# Arduino-Pro-Mini-v10.net
KiCad netlist of a schematic drawn in EAGLE
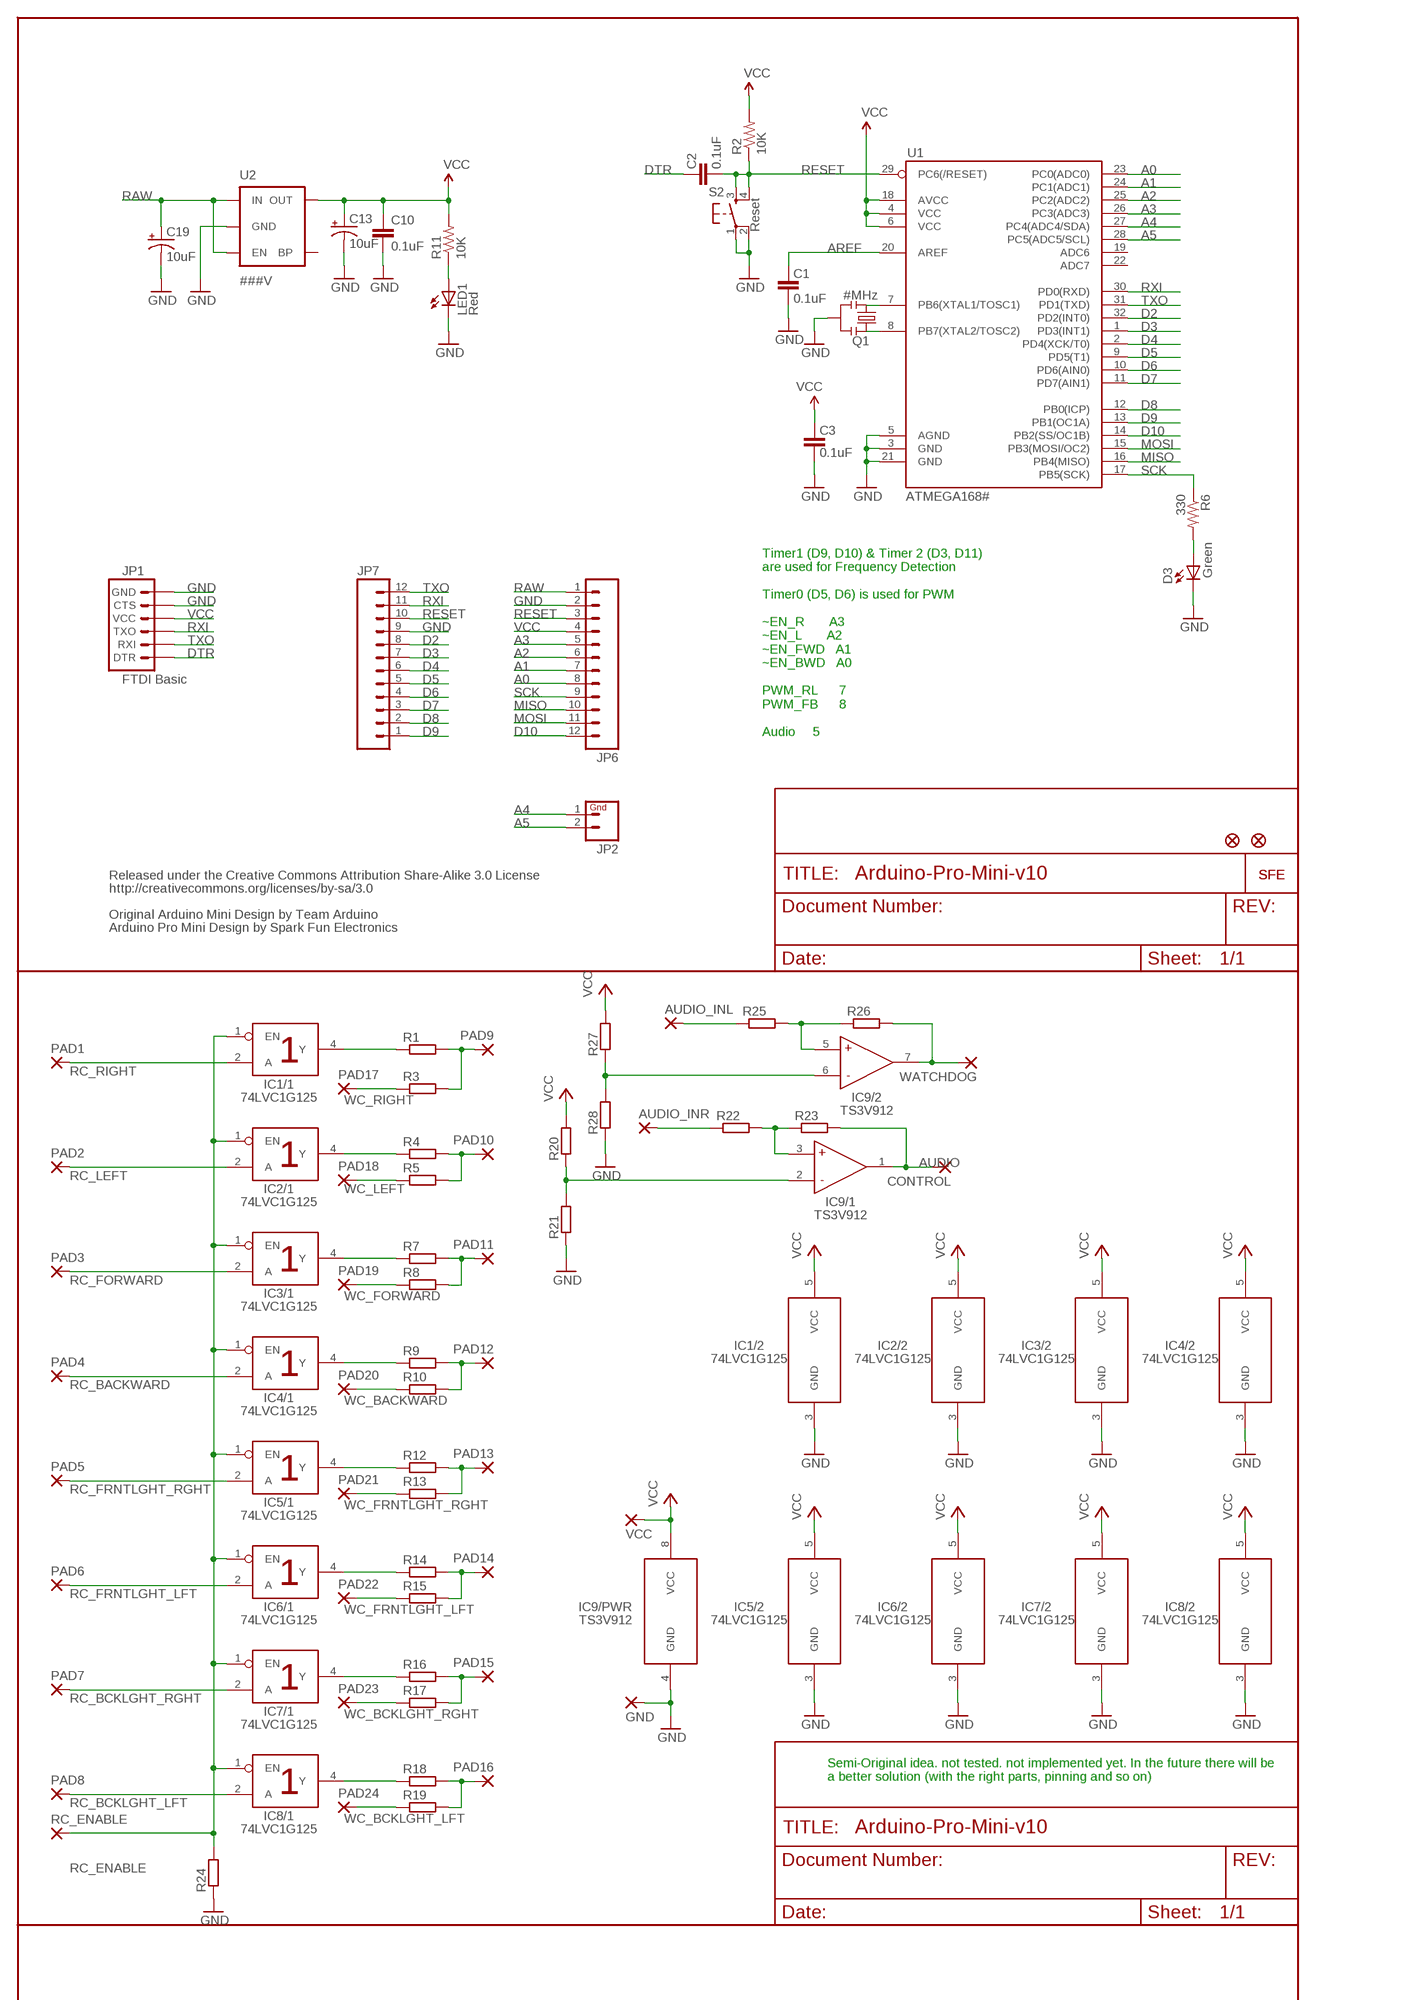
[diagram p0: schematic, sheet 1, part 1 of 2]
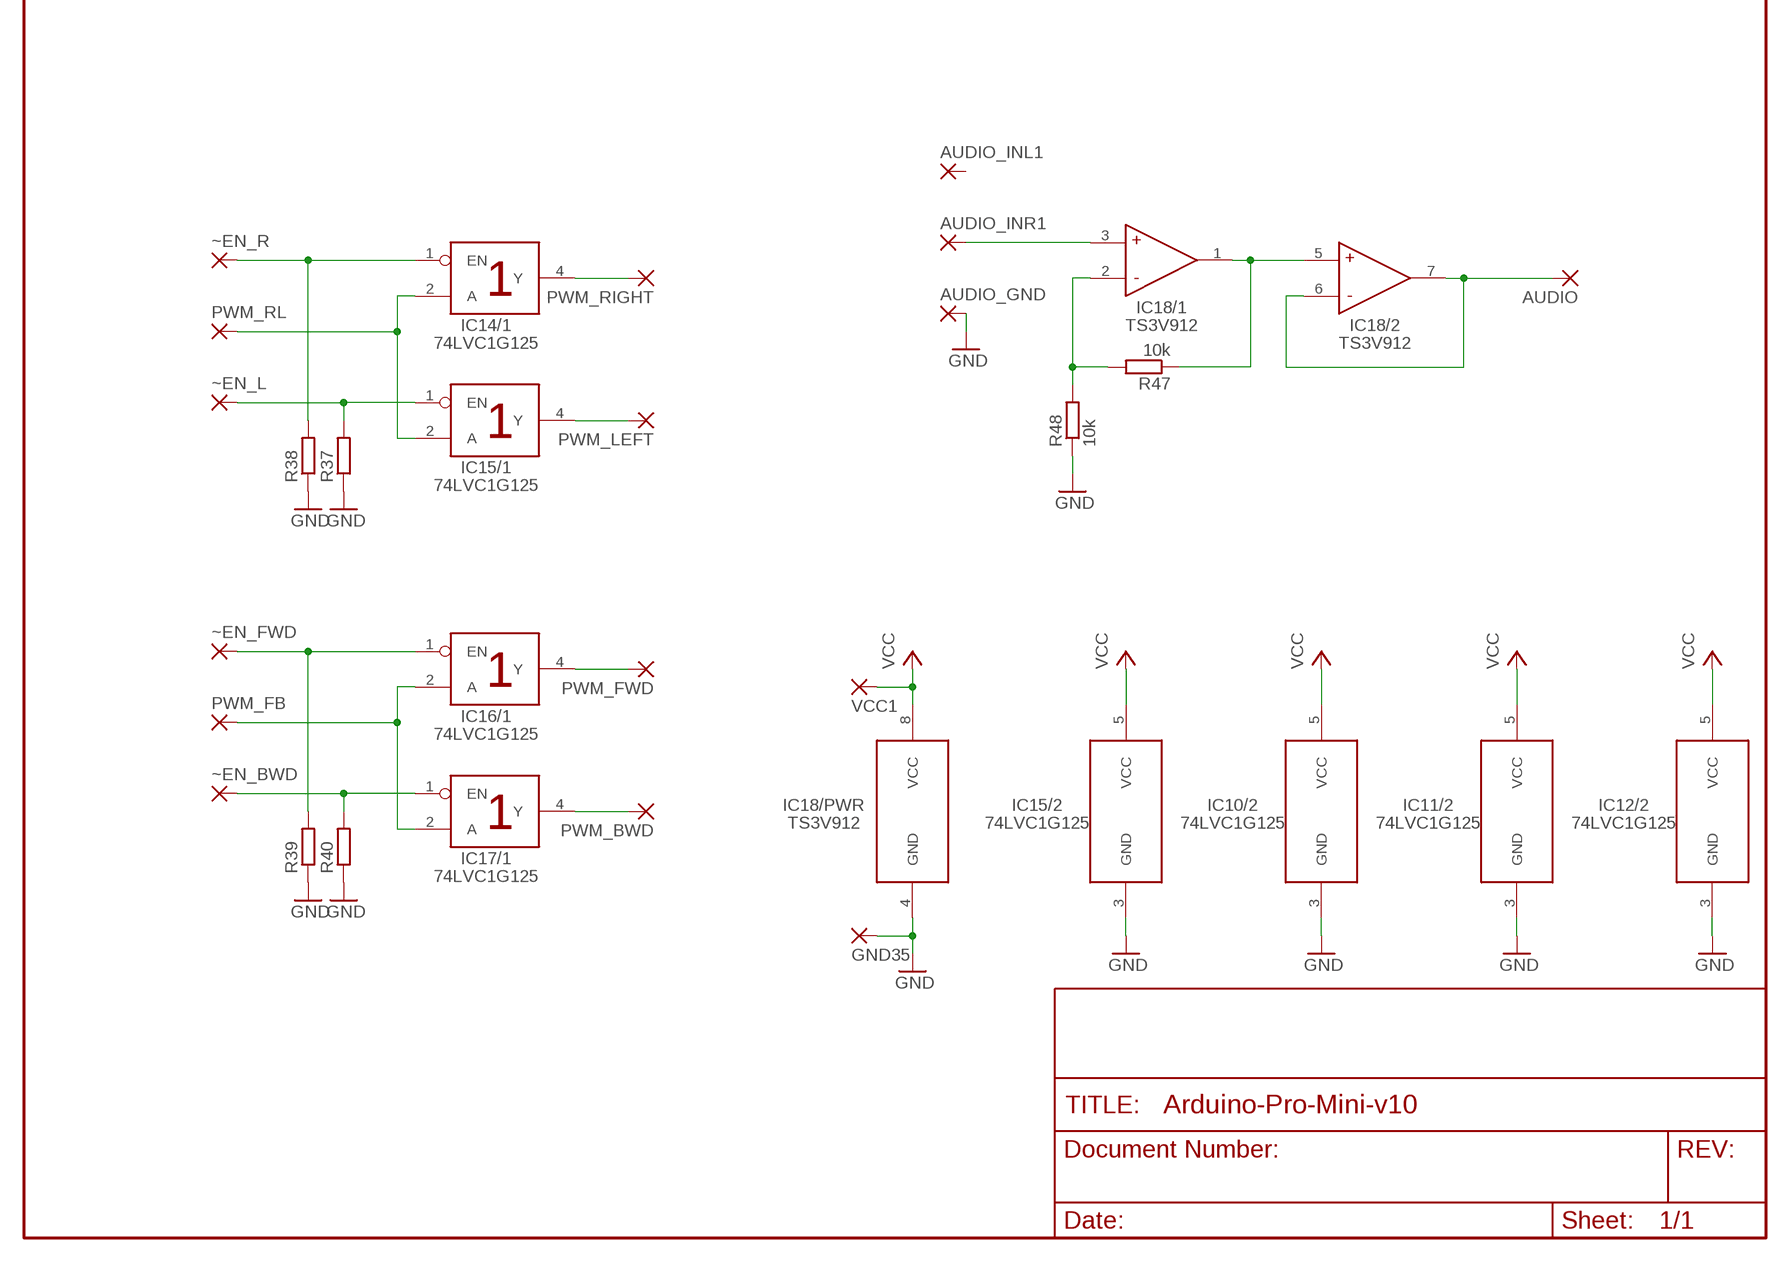
[diagram p1: schematic, sheet 1, part 2 of 2]

(export (version "E")
  (design (tool "Eeschema 10.0.6"))
  (components
    (comp (ref "AUDIO")
      (value "SMD2")
      (footprint "eagle-import:SMD1,27-2,54")
      (libsource (lib "eagle-import") (part "SMD2"))
    )
    (comp (ref "AUDIO_GND")
      (value "SMD2")
      (footprint "eagle-import:SMD1,27-2,54")
      (libsource (lib "eagle-import") (part "SMD2"))
    )
    (comp (ref "AUDIO_INL")
      (value "SMD2")
      (footprint "eagle-import:SMD1,27-2,54")
      (libsource (lib "eagle-import") (part "SMD2"))
    )
    (comp (ref "AUDIO_INL1")
      (value "SMD2")
      (footprint "eagle-import:SMD1,27-2,54")
      (libsource (lib "eagle-import") (part "SMD2"))
    )
    (comp (ref "AUDIO_INR")
      (value "SMD2")
      (footprint "eagle-import:SMD1,27-2,54")
      (libsource (lib "eagle-import") (part "SMD2"))
    )
    (comp (ref "AUDIO_INR1")
      (value "SMD2")
      (footprint "eagle-import:SMD1,27-2,54")
      (libsource (lib "eagle-import") (part "SMD2"))
    )
    (comp (ref "C1")
      (value "0.1uF")
      (footprint "eagle-import:C0402")
      (libsource (lib "eagle-import") (part "CAP0402"))
    )
    (comp (ref "C2")
      (value "0.1uF")
      (footprint "eagle-import:C0402")
      (libsource (lib "eagle-import") (part "CAP0402"))
    )
    (comp (ref "C3")
      (value "0.1uF")
      (footprint "eagle-import:C0402")
      (libsource (lib "eagle-import") (part "CAP0402"))
    )
    (comp (ref "C10")
      (value "0.1uF")
      (footprint "eagle-import:C0402")
      (libsource (lib "eagle-import") (part "CAP0402"))
    )
    (comp (ref "C13")
      (value "10uF")
      (footprint "eagle-import:EIA3216")
      (libsource (lib "eagle-import") (part "CAP_POL1206"))
    )
    (comp (ref "C19")
      (value "10uF")
      (footprint "eagle-import:EIA3216")
      (libsource (lib "eagle-import") (part "CAP_POL1206"))
    )
    (comp (ref "CONTROL")
      (value "SMD2")
      (footprint "eagle-import:SMD1,27-2,54")
      (libsource (lib "eagle-import") (part "SMD2"))
    )
    (comp (ref "D3")
      (value "Green")
      (footprint "eagle-import:LED-0603")
      (libsource (lib "eagle-import") (part "LED0603"))
    )
    (comp (ref "GND")
      (value "SMD2")
      (footprint "eagle-import:SMD1,27-2,54")
      (libsource (lib "eagle-import") (part "SMD2"))
    )
    (comp (ref "GND35")
      (value "SMD2")
      (footprint "eagle-import:SMD1,27-2,54")
      (libsource (lib "eagle-import") (part "SMD2"))
    )
    (comp (ref "IC1")
      (value "74LVC1G125")
      (footprint "eagle-import:DBV_R-PDSO-G5")
      (libsource (lib "eagle-import") (part "74LVC1G125"))
    )
    (comp (ref "IC2")
      (value "74LVC1G125")
      (footprint "eagle-import:DBV_R-PDSO-G5")
      (libsource (lib "eagle-import") (part "74LVC1G125"))
    )
    (comp (ref "IC3")
      (value "74LVC1G125")
      (footprint "eagle-import:DBV_R-PDSO-G5")
      (libsource (lib "eagle-import") (part "74LVC1G125"))
    )
    (comp (ref "IC4")
      (value "74LVC1G125")
      (footprint "eagle-import:DBV_R-PDSO-G5")
      (libsource (lib "eagle-import") (part "74LVC1G125"))
    )
    (comp (ref "IC5")
      (value "74LVC1G125")
      (footprint "eagle-import:DBV_R-PDSO-G5")
      (libsource (lib "eagle-import") (part "74LVC1G125"))
    )
    (comp (ref "IC6")
      (value "74LVC1G125")
      (footprint "eagle-import:DBV_R-PDSO-G5")
      (libsource (lib "eagle-import") (part "74LVC1G125"))
    )
    (comp (ref "IC7")
      (value "74LVC1G125")
      (footprint "eagle-import:DBV_R-PDSO-G5")
      (libsource (lib "eagle-import") (part "74LVC1G125"))
    )
    (comp (ref "IC8")
      (value "74LVC1G125")
      (footprint "eagle-import:DBV_R-PDSO-G5")
      (libsource (lib "eagle-import") (part "74LVC1G125"))
    )
    (comp (ref "IC9")
      (value "TS3V912")
      (footprint "eagle-import:SO8")
      (libsource (lib "eagle-import") (part "TS3V912"))
    )
    (comp (ref "IC10")
      (value "74LVC1G125")
      (footprint "eagle-import:DBV_R-PDSO-G5")
      (libsource (lib "eagle-import") (part "74LVC1G125"))
    )
    (comp (ref "IC11")
      (value "74LVC1G125")
      (footprint "eagle-import:DBV_R-PDSO-G5")
      (libsource (lib "eagle-import") (part "74LVC1G125"))
    )
    (comp (ref "IC12")
      (value "74LVC1G125")
      (footprint "eagle-import:DBV_R-PDSO-G5")
      (libsource (lib "eagle-import") (part "74LVC1G125"))
    )
    (comp (ref "IC14")
      (value "74LVC1G125")
      (footprint "eagle-import:DBV_R-PDSO-G5")
      (libsource (lib "eagle-import") (part "74LVC1G125"))
    )
    (comp (ref "IC15")
      (value "74LVC1G125")
      (footprint "eagle-import:DBV_R-PDSO-G5")
      (libsource (lib "eagle-import") (part "74LVC1G125"))
    )
    (comp (ref "IC16")
      (value "74LVC1G125")
      (footprint "eagle-import:DBV_R-PDSO-G5")
      (libsource (lib "eagle-import") (part "74LVC1G125"))
    )
    (comp (ref "IC17")
      (value "74LVC1G125")
      (footprint "eagle-import:DBV_R-PDSO-G5")
      (libsource (lib "eagle-import") (part "74LVC1G125"))
    )
    (comp (ref "IC18")
      (value "TS3V912")
      (footprint "eagle-import:SO8")
      (libsource (lib "eagle-import") (part "TS3V912"))
    )
    (comp (ref "JP1")
      (value "FTDI Basic")
      (footprint "eagle-import:1X06")
      (libsource (lib "eagle-import") (part "ARDUINO_SERIAL_PROGRAMPTH"))
    )
    (comp (ref "JP2")
      (value "M02PTH")
      (footprint "eagle-import:1X02")
      (libsource (lib "eagle-import") (part "M02PTH"))
    )
    (comp (ref "JP6")
      (value "M12PTH")
      (footprint "eagle-import:1X12")
      (libsource (lib "eagle-import") (part "M12PTH"))
    )
    (comp (ref "JP7")
      (value "M12PTH")
      (footprint "eagle-import:1X12")
      (libsource (lib "eagle-import") (part "M12PTH"))
    )
    (comp (ref "LED1")
      (value "Red")
      (footprint "eagle-import:LED-0603")
      (libsource (lib "eagle-import") (part "LED0603"))
    )
    (comp (ref "PAD1")
      (value "SMD2")
      (footprint "eagle-import:SMD1,27-2,54")
      (libsource (lib "eagle-import") (part "SMD2"))
    )
    (comp (ref "PAD2")
      (value "SMD2")
      (footprint "eagle-import:SMD1,27-2,54")
      (libsource (lib "eagle-import") (part "SMD2"))
    )
    (comp (ref "PAD3")
      (value "SMD2")
      (footprint "eagle-import:SMD1,27-2,54")
      (libsource (lib "eagle-import") (part "SMD2"))
    )
    (comp (ref "PAD4")
      (value "SMD2")
      (footprint "eagle-import:SMD1,27-2,54")
      (libsource (lib "eagle-import") (part "SMD2"))
    )
    (comp (ref "PAD5")
      (value "SMD2")
      (footprint "eagle-import:SMD1,27-2,54")
      (libsource (lib "eagle-import") (part "SMD2"))
    )
    (comp (ref "PAD6")
      (value "SMD2")
      (footprint "eagle-import:SMD1,27-2,54")
      (libsource (lib "eagle-import") (part "SMD2"))
    )
    (comp (ref "PAD7")
      (value "SMD2")
      (footprint "eagle-import:SMD1,27-2,54")
      (libsource (lib "eagle-import") (part "SMD2"))
    )
    (comp (ref "PAD8")
      (value "SMD2")
      (footprint "eagle-import:SMD1,27-2,54")
      (libsource (lib "eagle-import") (part "SMD2"))
    )
    (comp (ref "PAD9")
      (value "SMD2")
      (footprint "eagle-import:SMD1,27-2,54")
      (libsource (lib "eagle-import") (part "SMD2"))
    )
    (comp (ref "PAD10")
      (value "SMD2")
      (footprint "eagle-import:SMD1,27-2,54")
      (libsource (lib "eagle-import") (part "SMD2"))
    )
    (comp (ref "PAD11")
      (value "SMD2")
      (footprint "eagle-import:SMD1,27-2,54")
      (libsource (lib "eagle-import") (part "SMD2"))
    )
    (comp (ref "PAD12")
      (value "SMD2")
      (footprint "eagle-import:SMD1,27-2,54")
      (libsource (lib "eagle-import") (part "SMD2"))
    )
    (comp (ref "PAD13")
      (value "SMD2")
      (footprint "eagle-import:SMD1,27-2,54")
      (libsource (lib "eagle-import") (part "SMD2"))
    )
    (comp (ref "PAD14")
      (value "SMD2")
      (footprint "eagle-import:SMD1,27-2,54")
      (libsource (lib "eagle-import") (part "SMD2"))
    )
    (comp (ref "PAD15")
      (value "SMD2")
      (footprint "eagle-import:SMD1,27-2,54")
      (libsource (lib "eagle-import") (part "SMD2"))
    )
    (comp (ref "PAD16")
      (value "SMD2")
      (footprint "eagle-import:SMD1,27-2,54")
      (libsource (lib "eagle-import") (part "SMD2"))
    )
    (comp (ref "PAD17")
      (value "SMD2")
      (footprint "eagle-import:SMD1,27-2,54")
      (libsource (lib "eagle-import") (part "SMD2"))
    )
    (comp (ref "PAD18")
      (value "SMD2")
      (footprint "eagle-import:SMD1,27-2,54")
      (libsource (lib "eagle-import") (part "SMD2"))
    )
    (comp (ref "PAD19")
      (value "SMD2")
      (footprint "eagle-import:SMD1,27-2,54")
      (libsource (lib "eagle-import") (part "SMD2"))
    )
    (comp (ref "PAD20")
      (value "SMD2")
      (footprint "eagle-import:SMD1,27-2,54")
      (libsource (lib "eagle-import") (part "SMD2"))
    )
    (comp (ref "PAD21")
      (value "SMD2")
      (footprint "eagle-import:SMD1,27-2,54")
      (libsource (lib "eagle-import") (part "SMD2"))
    )
    (comp (ref "PAD22")
      (value "SMD2")
      (footprint "eagle-import:SMD1,27-2,54")
      (libsource (lib "eagle-import") (part "SMD2"))
    )
    (comp (ref "PAD23")
      (value "SMD2")
      (footprint "eagle-import:SMD1,27-2,54")
      (libsource (lib "eagle-import") (part "SMD2"))
    )
    (comp (ref "PAD24")
      (value "SMD2")
      (footprint "eagle-import:SMD1,27-2,54")
      (libsource (lib "eagle-import") (part "SMD2"))
    )
    (comp (ref "PWM_BWD")
      (value "SMD2")
      (footprint "eagle-import:SMD1,27-2,54")
      (libsource (lib "eagle-import") (part "SMD2"))
    )
    (comp (ref "PWM_FB")
      (value "SMD2")
      (footprint "eagle-import:SMD1,27-2,54")
      (libsource (lib "eagle-import") (part "SMD2"))
    )
    (comp (ref "PWM_FWD")
      (value "SMD2")
      (footprint "eagle-import:SMD1,27-2,54")
      (libsource (lib "eagle-import") (part "SMD2"))
    )
    (comp (ref "PWM_LEFT")
      (value "SMD2")
      (footprint "eagle-import:SMD1,27-2,54")
      (libsource (lib "eagle-import") (part "SMD2"))
    )
    (comp (ref "PWM_RIGHT")
      (value "SMD2")
      (footprint "eagle-import:SMD1,27-2,54")
      (libsource (lib "eagle-import") (part "SMD2"))
    )
    (comp (ref "PWM_RL")
      (value "SMD2")
      (footprint "eagle-import:SMD1,27-2,54")
      (libsource (lib "eagle-import") (part "SMD2"))
    )
    (comp (ref "Q1")
      (value "#MHz")
      (footprint "eagle-import:RESONATOR-SMD")
      (libsource (lib "eagle-import") (part "RESONATORSMD"))
    )
    (comp (ref "R1")
      (value "R-EU_M0805")
      (footprint "eagle-import:M0805")
      (libsource (lib "eagle-import") (part "R-EU_M0805"))
    )
    (comp (ref "R2")
      (value "10K")
      (footprint "eagle-import:C0402")
      (libsource (lib "eagle-import") (part "RESISTOR0402"))
    )
    (comp (ref "R3")
      (value "R-EU_M0805")
      (footprint "eagle-import:M0805")
      (libsource (lib "eagle-import") (part "R-EU_M0805"))
    )
    (comp (ref "R4")
      (value "R-EU_M0805")
      (footprint "eagle-import:M0805")
      (libsource (lib "eagle-import") (part "R-EU_M0805"))
    )
    (comp (ref "R5")
      (value "R-EU_M0805")
      (footprint "eagle-import:M0805")
      (libsource (lib "eagle-import") (part "R-EU_M0805"))
    )
    (comp (ref "R6")
      (value "330")
      (footprint "eagle-import:C0402")
      (libsource (lib "eagle-import") (part "RESISTOR0402"))
    )
    (comp (ref "R7")
      (value "R-EU_M0805")
      (footprint "eagle-import:M0805")
      (libsource (lib "eagle-import") (part "R-EU_M0805"))
    )
    (comp (ref "R8")
      (value "R-EU_M0805")
      (footprint "eagle-import:M0805")
      (libsource (lib "eagle-import") (part "R-EU_M0805"))
    )
    (comp (ref "R9")
      (value "R-EU_M0805")
      (footprint "eagle-import:M0805")
      (libsource (lib "eagle-import") (part "R-EU_M0805"))
    )
    (comp (ref "R10")
      (value "R-EU_M0805")
      (footprint "eagle-import:M0805")
      (libsource (lib "eagle-import") (part "R-EU_M0805"))
    )
    (comp (ref "R11")
      (value "10K")
      (footprint "eagle-import:C0402")
      (libsource (lib "eagle-import") (part "RESISTOR0402"))
    )
    (comp (ref "R12")
      (value "R-EU_M0805")
      (footprint "eagle-import:M0805")
      (libsource (lib "eagle-import") (part "R-EU_M0805"))
    )
    (comp (ref "R13")
      (value "R-EU_M0805")
      (footprint "eagle-import:M0805")
      (libsource (lib "eagle-import") (part "R-EU_M0805"))
    )
    (comp (ref "R14")
      (value "R-EU_M0805")
      (footprint "eagle-import:M0805")
      (libsource (lib "eagle-import") (part "R-EU_M0805"))
    )
    (comp (ref "R15")
      (value "R-EU_M0805")
      (footprint "eagle-import:M0805")
      (libsource (lib "eagle-import") (part "R-EU_M0805"))
    )
    (comp (ref "R16")
      (value "R-EU_M0805")
      (footprint "eagle-import:M0805")
      (libsource (lib "eagle-import") (part "R-EU_M0805"))
    )
    (comp (ref "R17")
      (value "R-EU_M0805")
      (footprint "eagle-import:M0805")
      (libsource (lib "eagle-import") (part "R-EU_M0805"))
    )
    (comp (ref "R18")
      (value "R-EU_M0805")
      (footprint "eagle-import:M0805")
      (libsource (lib "eagle-import") (part "R-EU_M0805"))
    )
    (comp (ref "R19")
      (value "R-EU_M0805")
      (footprint "eagle-import:M0805")
      (libsource (lib "eagle-import") (part "R-EU_M0805"))
    )
    (comp (ref "R20")
      (value "R-EU_M0805")
      (footprint "eagle-import:M0805")
      (libsource (lib "eagle-import") (part "R-EU_M0805"))
    )
    (comp (ref "R21")
      (value "R-EU_M0805")
      (footprint "eagle-import:M0805")
      (libsource (lib "eagle-import") (part "R-EU_M0805"))
    )
    (comp (ref "R22")
      (value "R-EU_M0805")
      (footprint "eagle-import:M0805")
      (libsource (lib "eagle-import") (part "R-EU_M0805"))
    )
    (comp (ref "R23")
      (value "R-EU_M0805")
      (footprint "eagle-import:M0805")
      (libsource (lib "eagle-import") (part "R-EU_M0805"))
    )
    (comp (ref "R24")
      (value "R-EU_M0805")
      (footprint "eagle-import:M0805")
      (libsource (lib "eagle-import") (part "R-EU_M0805"))
    )
    (comp (ref "R25")
      (value "R-EU_M0805")
      (footprint "eagle-import:M0805")
      (libsource (lib "eagle-import") (part "R-EU_M0805"))
    )
    (comp (ref "R26")
      (value "R-EU_M0805")
      (footprint "eagle-import:M0805")
      (libsource (lib "eagle-import") (part "R-EU_M0805"))
    )
    (comp (ref "R27")
      (value "R-EU_M0805")
      (footprint "eagle-import:M0805")
      (libsource (lib "eagle-import") (part "R-EU_M0805"))
    )
    (comp (ref "R28")
      (value "R-EU_M0805")
      (footprint "eagle-import:M0805")
      (libsource (lib "eagle-import") (part "R-EU_M0805"))
    )
    (comp (ref "R37")
      (value "R-EU_M0805")
      (footprint "eagle-import:M0805")
      (libsource (lib "eagle-import") (part "R-EU_M0805"))
    )
    (comp (ref "R38")
      (value "R-EU_M0805")
      (footprint "eagle-import:M0805")
      (libsource (lib "eagle-import") (part "R-EU_M0805"))
    )
    (comp (ref "R39")
      (value "R-EU_M0805")
      (footprint "eagle-import:M0805")
      (libsource (lib "eagle-import") (part "R-EU_M0805"))
    )
    (comp (ref "R40")
      (value "R-EU_M0805")
      (footprint "eagle-import:M0805")
      (libsource (lib "eagle-import") (part "R-EU_M0805"))
    )
    (comp (ref "R47")
      (value "10k")
      (footprint "eagle-import:M0805")
      (libsource (lib "eagle-import") (part "R-EU_M0805"))
    )
    (comp (ref "R48")
      (value "10k")
      (footprint "eagle-import:M0805")
      (libsource (lib "eagle-import") (part "R-EU_M0805"))
    )
    (comp (ref "RC_ENABLE")
      (value "SMD2")
      (footprint "eagle-import:SMD1,27-2,54")
      (libsource (lib "eagle-import") (part "SMD2"))
    )
    (comp (ref "S2")
      (value "Reset")
      (footprint "eagle-import:TACTILE_SWITCH_SMD")
      (libsource (lib "eagle-import") (part "TAC_SWITCHSND"))
    )
    (comp (ref "U$1")
      (value "LOGO-SFESK")
      (footprint "eagle-import:SFE-LOGO-FLAME")
      (libsource (lib "eagle-import") (part "LOGO-SFESK"))
    )
    (comp (ref "U$2")
      (value "FIDUCIAL1X2")
      (footprint "eagle-import:FIDUCIAL-1X2")
      (libsource (lib "eagle-import") (part "FIDUCIAL1X2"))
    )
    (comp (ref "U$4")
      (value "FIDUCIAL1X2")
      (footprint "eagle-import:FIDUCIAL-1X2")
      (libsource (lib "eagle-import") (part "FIDUCIAL1X2"))
    )
    (comp (ref "U$11")
      (value "LOGO-SFENEW")
      (footprint "eagle-import:SFE-NEW-WEBLOGO")
      (libsource (lib "eagle-import") (part "LOGO-SFENEW"))
    )
    (comp (ref "U1")
      (value "ATMEGA168#")
      (footprint "eagle-import:TQFP32-08")
      (libsource (lib "eagle-import") (part "ATMEGA168"))
    )
    (comp (ref "U2")
      (value "###V")
      (footprint "eagle-import:SOT23-5")
      (libsource (lib "eagle-import") (part "V_REG_LDOSMD"))
    )
    (comp (ref "VCC")
      (value "SMD2")
      (footprint "eagle-import:SMD1,27-2,54")
      (libsource (lib "eagle-import") (part "SMD2"))
    )
    (comp (ref "VCC1")
      (value "SMD2")
      (footprint "eagle-import:SMD1,27-2,54")
      (libsource (lib "eagle-import") (part "SMD2"))
    )
    (comp (ref "WATCHDOG")
      (value "SMD2")
      (footprint "eagle-import:SMD1,27-2,54")
      (libsource (lib "eagle-import") (part "SMD2"))
    )
    (comp (ref "~EN_BWD")
      (value "SMD2")
      (footprint "eagle-import:SMD1,27-2,54")
      (libsource (lib "eagle-import") (part "SMD2"))
    )
    (comp (ref "~EN_FWD")
      (value "SMD2")
      (footprint "eagle-import:SMD1,27-2,54")
      (libsource (lib "eagle-import") (part "SMD2"))
    )
    (comp (ref "~EN_L")
      (value "SMD2")
      (footprint "eagle-import:SMD1,27-2,54")
      (libsource (lib "eagle-import") (part "SMD2"))
    )
    (comp (ref "~EN_R")
      (value "SMD2")
      (footprint "eagle-import:SMD1,27-2,54")
      (libsource (lib "eagle-import") (part "SMD2"))
    )
  )
  (nets
    (net (code "1") (name "/A0") (class "Default")
      (node (ref "JP6") (pin "8") (pinfunction "8_8") (pintype "passive"))
      (node (ref "U1") (pin "23") (pinfunction "PC0(ADC0)_23") (pintype "bidirectional"))
    )
    (net (code "2") (name "/A1") (class "Default")
      (node (ref "JP6") (pin "7") (pinfunction "7_7") (pintype "passive"))
      (node (ref "U1") (pin "24") (pinfunction "PC1(ADC1)_24") (pintype "bidirectional"))
    )
    (net (code "3") (name "/A2") (class "Default")
      (node (ref "JP6") (pin "6") (pinfunction "6_6") (pintype "passive"))
      (node (ref "U1") (pin "25") (pinfunction "PC2(ADC2)_25") (pintype "bidirectional"))
    )
    (net (code "4") (name "/A3") (class "Default")
      (node (ref "JP6") (pin "5") (pinfunction "5_5") (pintype "passive"))
      (node (ref "U1") (pin "26") (pinfunction "PC3(ADC3)_26") (pintype "bidirectional"))
    )
    (net (code "5") (name "/A4") (class "Default")
      (node (ref "JP2") (pin "1") (pinfunction "1_1") (pintype "passive"))
      (node (ref "U1") (pin "27") (pinfunction "PC4(ADC4/SDA)_27") (pintype "bidirectional"))
    )
    (net (code "6") (name "/A5") (class "Default")
      (node (ref "JP2") (pin "2") (pinfunction "2_2") (pintype "passive"))
      (node (ref "U1") (pin "28") (pinfunction "PC5(ADC5/SCL)_28") (pintype "bidirectional"))
    )
    (net (code "7") (name "/AREF") (class "Default")
      (node (ref "C1") (pin "2") (pinfunction "2_2") (pintype "passive"))
      (node (ref "U1") (pin "20") (pinfunction "AREF_20") (pintype "bidirectional"))
    )
    (net (code "8") (name "/AUDIO") (class "Default")
      (node (ref "AUDIO") (pin "1") (pinfunction "P_1") (pintype "passive"))
      (node (ref "CONTROL") (pin "1") (pinfunction "P_1") (pintype "passive"))
      (node (ref "IC18") (pin "6") (pinfunction "-_6") (pintype "bidirectional"))
      (node (ref "IC18") (pin "7") (pinfunction "OUT_7") (pintype "bidirectional"))
      (node (ref "IC9") (pin "1") (pinfunction "OUT_1") (pintype "bidirectional"))
      (node (ref "R23") (pin "2") (pinfunction "2_2") (pintype "passive"))
    )
    (net (code "9") (name "/D2") (class "Default")
      (node (ref "JP7") (pin "8") (pinfunction "8_8") (pintype "passive"))
      (node (ref "U1") (pin "32") (pinfunction "PD2(INT0)_32") (pintype "bidirectional"))
    )
    (net (code "10") (name "/D3") (class "Default")
      (node (ref "JP7") (pin "7") (pinfunction "7_7") (pintype "passive"))
      (node (ref "U1") (pin "1") (pinfunction "PD3(INT1)_1") (pintype "bidirectional"))
    )
    (net (code "11") (name "/D4") (class "Default")
      (node (ref "JP7") (pin "6") (pinfunction "6_6") (pintype "passive"))
      (node (ref "U1") (pin "2") (pinfunction "PD4(XCK/T0)_2") (pintype "bidirectional"))
    )
    (net (code "12") (name "/D5") (class "Default")
      (node (ref "JP7") (pin "5") (pinfunction "5_5") (pintype "passive"))
      (node (ref "U1") (pin "9") (pinfunction "PD5(T1)_9") (pintype "bidirectional"))
    )
    (net (code "13") (name "/D6") (class "Default")
      (node (ref "JP7") (pin "4") (pinfunction "4_4") (pintype "passive"))
      (node (ref "U1") (pin "10") (pinfunction "PD6(AIN0)_10") (pintype "bidirectional"))
    )
    (net (code "14") (name "/D7") (class "Default")
      (node (ref "JP7") (pin "3") (pinfunction "3_3") (pintype "passive"))
      (node (ref "U1") (pin "11") (pinfunction "PD7(AIN1)_11") (pintype "bidirectional"))
    )
    (net (code "15") (name "/D8") (class "Default")
      (node (ref "JP7") (pin "2") (pinfunction "2_2") (pintype "passive"))
      (node (ref "U1") (pin "12") (pinfunction "PB0(ICP)_12") (pintype "bidirectional"))
    )
    (net (code "16") (name "/D9") (class "Default")
      (node (ref "JP7") (pin "1") (pinfunction "1_1") (pintype "passive"))
      (node (ref "U1") (pin "13") (pinfunction "PB1(OC1A)_13") (pintype "bidirectional"))
    )
    (net (code "17") (name "/D10") (class "Default")
      (node (ref "JP6") (pin "12") (pinfunction "12_12") (pintype "passive"))
      (node (ref "U1") (pin "14") (pinfunction "PB2(SS/OC1B)_14") (pintype "bidirectional"))
    )
    (net (code "18") (name "/DTR") (class "Default")
      (node (ref "C2") (pin "2") (pinfunction "2_2") (pintype "passive"))
      (node (ref "JP1") (pin "1") (pinfunction "DTR_1") (pintype "passive"))
    )
    (net (code "19") (name "/MISO") (class "Default")
      (node (ref "JP6") (pin "10") (pinfunction "10_10") (pintype "passive"))
      (node (ref "U1") (pin "16") (pinfunction "PB4(MISO)_16") (pintype "bidirectional"))
    )
    (net (code "20") (name "/MOSI") (class "Default")
      (node (ref "JP6") (pin "11") (pinfunction "11_11") (pintype "passive"))
      (node (ref "U1") (pin "15") (pinfunction "PB3(MOSI/OC2)_15") (pintype "bidirectional"))
    )
    (net (code "21") (name "/RAW") (class "Default")
      (node (ref "C19") (pin "A") (pinfunction "+_A") (pintype "passive"))
      (node (ref "JP6") (pin "1") (pinfunction "1_1") (pintype "passive"))
      (node (ref "U2") (pin "1") (pinfunction "IN_1") (pintype "input"))
      (node (ref "U2") (pin "3") (pinfunction "EN_3") (pintype "input"))
    )
    (net (code "22") (name "/RC_BACKWARD") (class "Default")
      (node (ref "IC4") (pin "2") (pinfunction "A_2") (pintype "bidirectional"))
      (node (ref "PAD4") (pin "1") (pinfunction "P_1") (pintype "passive"))
    )
    (net (code "23") (name "/RC_BCKLGHT_LFT") (class "Default")
      (node (ref "IC8") (pin "2") (pinfunction "A_2") (pintype "bidirectional"))
      (node (ref "PAD8") (pin "1") (pinfunction "P_1") (pintype "passive"))
    )
    (net (code "24") (name "/RC_BCKLGHT_RGHT") (class "Default")
      (node (ref "IC7") (pin "2") (pinfunction "A_2") (pintype "bidirectional"))
      (node (ref "PAD7") (pin "1") (pinfunction "P_1") (pintype "passive"))
    )
    (net (code "25") (name "/RC_ENABLE") (class "Default")
      (node (ref "IC1") (pin "1") (pinfunction "EN_1") (pintype "bidirectional"))
      (node (ref "IC2") (pin "1") (pinfunction "EN_1") (pintype "bidirectional"))
      (node (ref "IC3") (pin "1") (pinfunction "EN_1") (pintype "bidirectional"))
      (node (ref "IC4") (pin "1") (pinfunction "EN_1") (pintype "bidirectional"))
      (node (ref "IC5") (pin "1") (pinfunction "EN_1") (pintype "bidirectional"))
      (node (ref "IC6") (pin "1") (pinfunction "EN_1") (pintype "bidirectional"))
      (node (ref "IC7") (pin "1") (pinfunction "EN_1") (pintype "bidirectional"))
      (node (ref "IC8") (pin "1") (pinfunction "EN_1") (pintype "bidirectional"))
      (node (ref "R24") (pin "2") (pinfunction "2_2") (pintype "passive"))
      (node (ref "RC_ENABLE") (pin "1") (pinfunction "P_1") (pintype "passive"))
    )
    (net (code "26") (name "/RC_FORWARD") (class "Default")
      (node (ref "IC3") (pin "2") (pinfunction "A_2") (pintype "bidirectional"))
      (node (ref "PAD3") (pin "1") (pinfunction "P_1") (pintype "passive"))
    )
    (net (code "27") (name "/RC_FRNTLGHT_LFT") (class "Default")
      (node (ref "IC6") (pin "2") (pinfunction "A_2") (pintype "bidirectional"))
      (node (ref "PAD6") (pin "1") (pinfunction "P_1") (pintype "passive"))
    )
    (net (code "28") (name "/RC_FRNTLGHT_RGHT") (class "Default")
      (node (ref "IC5") (pin "2") (pinfunction "A_2") (pintype "bidirectional"))
      (node (ref "PAD5") (pin "1") (pinfunction "P_1") (pintype "passive"))
    )
    (net (code "29") (name "/RC_LEFT") (class "Default")
      (node (ref "IC2") (pin "2") (pinfunction "A_2") (pintype "bidirectional"))
      (node (ref "PAD2") (pin "1") (pinfunction "P_1") (pintype "passive"))
    )
    (net (code "30") (name "/RC_RIGHT") (class "Default")
      (node (ref "IC1") (pin "2") (pinfunction "A_2") (pintype "bidirectional"))
      (node (ref "PAD1") (pin "1") (pinfunction "P_1") (pintype "passive"))
    )
    (net (code "31") (name "/RESET") (class "Default")
      (node (ref "C2") (pin "1") (pinfunction "1_1") (pintype "passive"))
      (node (ref "JP6") (pin "3") (pinfunction "3_3") (pintype "passive"))
      (node (ref "JP7") (pin "10") (pinfunction "10_10") (pintype "passive"))
      (node (ref "R2") (pin "1") (pinfunction "1_1") (pintype "passive"))
      (node (ref "S2") (pin "3") (pinfunction "3_3") (pintype "passive"))
      (node (ref "S2") (pin "4") (pinfunction "4_4") (pintype "passive"))
      (node (ref "U1") (pin "29") (pinfunction "PC6(/RESET)_29") (pintype "bidirectional"))
    )
    (net (code "32") (name "/RXI") (class "Default")
      (node (ref "JP1") (pin "3") (pinfunction "TXO_3") (pintype "passive"))
      (node (ref "JP7") (pin "11") (pinfunction "11_11") (pintype "passive"))
      (node (ref "U1") (pin "30") (pinfunction "PD0(RXD)_30") (pintype "bidirectional"))
    )
    (net (code "33") (name "/SCK") (class "Default")
      (node (ref "JP6") (pin "9") (pinfunction "9_9") (pintype "passive"))
      (node (ref "R6") (pin "1") (pinfunction "1_1") (pintype "passive"))
      (node (ref "U1") (pin "17") (pinfunction "PB5(SCK)_17") (pintype "bidirectional"))
    )
    (net (code "34") (name "/TXO") (class "Default")
      (node (ref "JP1") (pin "2") (pinfunction "RXI_2") (pintype "passive"))
      (node (ref "JP7") (pin "12") (pinfunction "12_12") (pintype "passive"))
      (node (ref "U1") (pin "31") (pinfunction "PD1(TXD)_31") (pintype "bidirectional"))
    )
    (net (code "35") (name "/WC_BACKWARD") (class "Default")
      (node (ref "PAD20") (pin "1") (pinfunction "P_1") (pintype "passive"))
      (node (ref "R10") (pin "1") (pinfunction "1_1") (pintype "passive"))
    )
    (net (code "36") (name "/WC_BCKLGHT_LFT") (class "Default")
      (node (ref "PAD24") (pin "1") (pinfunction "P_1") (pintype "passive"))
      (node (ref "R19") (pin "1") (pinfunction "1_1") (pintype "passive"))
    )
    (net (code "37") (name "/WC_BCKLGHT_RGHT") (class "Default")
      (node (ref "PAD23") (pin "1") (pinfunction "P_1") (pintype "passive"))
      (node (ref "R17") (pin "1") (pinfunction "1_1") (pintype "passive"))
    )
    (net (code "38") (name "/WC_FORWARD") (class "Default")
      (node (ref "PAD19") (pin "1") (pinfunction "P_1") (pintype "passive"))
      (node (ref "R8") (pin "1") (pinfunction "1_1") (pintype "passive"))
    )
    (net (code "39") (name "/WC_FRNTLGHT_LFT") (class "Default")
      (node (ref "PAD22") (pin "1") (pinfunction "P_1") (pintype "passive"))
      (node (ref "R15") (pin "1") (pinfunction "1_1") (pintype "passive"))
    )
    (net (code "40") (name "/WC_FRNTLGHT_RGHT") (class "Default")
      (node (ref "PAD21") (pin "1") (pinfunction "P_1") (pintype "passive"))
      (node (ref "R13") (pin "1") (pinfunction "1_1") (pintype "passive"))
    )
    (net (code "41") (name "/WC_LEFT") (class "Default")
      (node (ref "PAD18") (pin "1") (pinfunction "P_1") (pintype "passive"))
      (node (ref "R5") (pin "1") (pinfunction "1_1") (pintype "passive"))
    )
    (net (code "42") (name "/WC_RIGHT") (class "Default")
      (node (ref "PAD17") (pin "1") (pinfunction "P_1") (pintype "passive"))
      (node (ref "R3") (pin "1") (pinfunction "1_1") (pintype "passive"))
    )
    (net (code "43") (name "GND") (class "Default")
      (node (ref "AUDIO_GND") (pin "1") (pinfunction "P_1") (pintype "passive"))
      (node (ref "C1") (pin "1") (pinfunction "1_1") (pintype "passive"))
      (node (ref "C10") (pin "2") (pinfunction "2_2") (pintype "passive"))
      (node (ref "C13") (pin "C") (pinfunction "-_C") (pintype "passive"))
      (node (ref "C19") (pin "C") (pinfunction "-_C") (pintype "passive"))
      (node (ref "C3") (pin "1") (pinfunction "1_1") (pintype "passive"))
      (node (ref "D3") (pin "C") (pinfunction "C_C") (pintype "passive"))
      (node (ref "GND") (pin "1") (pinfunction "P_1") (pintype "passive"))
      (node (ref "GND35") (pin "1") (pinfunction "P_1") (pintype "passive"))
      (node (ref "IC1") (pin "3") (pinfunction "GND_3") (pintype "bidirectional"))
      (node (ref "IC10") (pin "3") (pinfunction "GND_3") (pintype "bidirectional"))
      (node (ref "IC11") (pin "3") (pinfunction "GND_3") (pintype "bidirectional"))
      (node (ref "IC12") (pin "3") (pinfunction "GND_3") (pintype "bidirectional"))
      (node (ref "IC15") (pin "3") (pinfunction "GND_3") (pintype "bidirectional"))
      (node (ref "IC18") (pin "4") (pinfunction "GND_4") (pintype "bidirectional"))
      (node (ref "IC2") (pin "3") (pinfunction "GND_3") (pintype "bidirectional"))
      (node (ref "IC3") (pin "3") (pinfunction "GND_3") (pintype "bidirectional"))
      (node (ref "IC4") (pin "3") (pinfunction "GND_3") (pintype "bidirectional"))
      (node (ref "IC5") (pin "3") (pinfunction "GND_3") (pintype "bidirectional"))
      (node (ref "IC6") (pin "3") (pinfunction "GND_3") (pintype "bidirectional"))
      (node (ref "IC7") (pin "3") (pinfunction "GND_3") (pintype "bidirectional"))
      (node (ref "IC8") (pin "3") (pinfunction "GND_3") (pintype "bidirectional"))
      (node (ref "IC9") (pin "4") (pinfunction "GND_4") (pintype "bidirectional"))
      (node (ref "JP1") (pin "5") (pinfunction "CTS_5") (pintype "passive"))
      (node (ref "JP1") (pin "6") (pinfunction "GND_6") (pintype "passive"))
      (node (ref "JP6") (pin "2") (pinfunction "2_2") (pintype "passive"))
      (node (ref "JP7") (pin "9") (pinfunction "9_9") (pintype "passive"))
      (node (ref "LED1") (pin "C") (pinfunction "C_C") (pintype "passive"))
      (node (ref "Q1") (pin "2") (pinfunction "2_2") (pintype "passive"))
      (node (ref "R21") (pin "1") (pinfunction "1_1") (pintype "passive"))
      (node (ref "R24") (pin "1") (pinfunction "1_1") (pintype "passive"))
      (node (ref "R28") (pin "1") (pinfunction "1_1") (pintype "passive"))
      (node (ref "R37") (pin "1") (pinfunction "1_1") (pintype "passive"))
      (node (ref "R38") (pin "1") (pinfunction "1_1") (pintype "passive"))
      (node (ref "R39") (pin "1") (pinfunction "1_1") (pintype "passive"))
      (node (ref "R40") (pin "1") (pinfunction "1_1") (pintype "passive"))
      (node (ref "R48") (pin "1") (pinfunction "1_1") (pintype "passive"))
      (node (ref "S2") (pin "1") (pinfunction "1_1") (pintype "passive"))
      (node (ref "S2") (pin "2") (pinfunction "2_2") (pintype "passive"))
      (node (ref "U1") (pin "21") (pinfunction "GND_21") (pintype "bidirectional"))
      (node (ref "U1") (pin "3") (pinfunction "GND_3") (pintype "bidirectional"))
      (node (ref "U1") (pin "5") (pinfunction "AGND_5") (pintype "bidirectional"))
      (node (ref "U2") (pin "2") (pinfunction "GND_2") (pintype "input"))
    )
    (net (code "44") (name "Net-(AUDIO_INL-P)") (class "Default")
      (node (ref "AUDIO_INL") (pin "1") (pinfunction "P_1") (pintype "passive"))
      (node (ref "R25") (pin "1") (pinfunction "1_1") (pintype "passive"))
    )
    (net (code "45") (name "Net-(AUDIO_INR-P)") (class "Default")
      (node (ref "AUDIO_INR") (pin "1") (pinfunction "P_1") (pintype "passive"))
      (node (ref "R22") (pin "1") (pinfunction "1_1") (pintype "passive"))
    )
    (net (code "46") (name "Net-(AUDIO_INR1-P)") (class "Default")
      (node (ref "AUDIO_INR1") (pin "1") (pinfunction "P_1") (pintype "passive"))
      (node (ref "IC18") (pin "3") (pinfunction "+_3") (pintype "bidirectional"))
    )
    (net (code "47") (name "Net-(D3-PadA)") (class "Default")
      (node (ref "D3") (pin "A") (pinfunction "A_A") (pintype "passive"))
      (node (ref "R6") (pin "2") (pinfunction "2_2") (pintype "passive"))
    )
    (net (code "48") (name "Net-(IC1A-Y)") (class "Default")
      (node (ref "IC1") (pin "4") (pinfunction "Y_4") (pintype "bidirectional"))
      (node (ref "R1") (pin "1") (pinfunction "1_1") (pintype "passive"))
    )
    (net (code "49") (name "Net-(IC2A-Y)") (class "Default")
      (node (ref "IC2") (pin "4") (pinfunction "Y_4") (pintype "bidirectional"))
      (node (ref "R4") (pin "1") (pinfunction "1_1") (pintype "passive"))
    )
    (net (code "50") (name "Net-(IC3A-Y)") (class "Default")
      (node (ref "IC3") (pin "4") (pinfunction "Y_4") (pintype "bidirectional"))
      (node (ref "R7") (pin "1") (pinfunction "1_1") (pintype "passive"))
    )
    (net (code "51") (name "Net-(IC4A-Y)") (class "Default")
      (node (ref "IC4") (pin "4") (pinfunction "Y_4") (pintype "bidirectional"))
      (node (ref "R9") (pin "1") (pinfunction "1_1") (pintype "passive"))
    )
    (net (code "52") (name "Net-(IC5A-Y)") (class "Default")
      (node (ref "IC5") (pin "4") (pinfunction "Y_4") (pintype "bidirectional"))
      (node (ref "R12") (pin "1") (pinfunction "1_1") (pintype "passive"))
    )
    (net (code "53") (name "Net-(IC6A-Y)") (class "Default")
      (node (ref "IC6") (pin "4") (pinfunction "Y_4") (pintype "bidirectional"))
      (node (ref "R14") (pin "1") (pinfunction "1_1") (pintype "passive"))
    )
    (net (code "54") (name "Net-(IC7A-Y)") (class "Default")
      (node (ref "IC7") (pin "4") (pinfunction "Y_4") (pintype "bidirectional"))
      (node (ref "R16") (pin "1") (pinfunction "1_1") (pintype "passive"))
    )
    (net (code "55") (name "Net-(IC8A-Y)") (class "Default")
      (node (ref "IC8") (pin "4") (pinfunction "Y_4") (pintype "bidirectional"))
      (node (ref "R18") (pin "1") (pinfunction "1_1") (pintype "passive"))
    )
    (net (code "56") (name "Net-(IC9A-+)") (class "Default")
      (node (ref "IC9") (pin "3") (pinfunction "+_3") (pintype "bidirectional"))
      (node (ref "R22") (pin "2") (pinfunction "2_2") (pintype "passive"))
      (node (ref "R23") (pin "1") (pinfunction "1_1") (pintype "passive"))
    )
    (net (code "57") (name "Net-(IC9A--)") (class "Default")
      (node (ref "IC9") (pin "2") (pinfunction "-_2") (pintype "bidirectional"))
      (node (ref "R20") (pin "1") (pinfunction "1_1") (pintype "passive"))
      (node (ref "R21") (pin "2") (pinfunction "2_2") (pintype "passive"))
    )
    (net (code "58") (name "Net-(IC9B-+)") (class "Default")
      (node (ref "IC9") (pin "5") (pinfunction "+_5") (pintype "bidirectional"))
      (node (ref "R25") (pin "2") (pinfunction "2_2") (pintype "passive"))
      (node (ref "R26") (pin "1") (pinfunction "1_1") (pintype "passive"))
    )
    (net (code "59") (name "Net-(IC9B--)") (class "Default")
      (node (ref "IC9") (pin "6") (pinfunction "-_6") (pintype "bidirectional"))
      (node (ref "R27") (pin "1") (pinfunction "1_1") (pintype "passive"))
      (node (ref "R28") (pin "2") (pinfunction "2_2") (pintype "passive"))
    )
    (net (code "60") (name "Net-(IC9B-OUT)") (class "Default")
      (node (ref "IC9") (pin "7") (pinfunction "OUT_7") (pintype "bidirectional"))
      (node (ref "R26") (pin "2") (pinfunction "2_2") (pintype "passive"))
      (node (ref "WATCHDOG") (pin "1") (pinfunction "P_1") (pintype "passive"))
    )
    (net (code "61") (name "Net-(IC14A-A)") (class "Default")
      (node (ref "IC14") (pin "2") (pinfunction "A_2") (pintype "bidirectional"))
      (node (ref "IC15") (pin "2") (pinfunction "A_2") (pintype "bidirectional"))
      (node (ref "PWM_RL") (pin "1") (pinfunction "P_1") (pintype "passive"))
    )
    (net (code "62") (name "Net-(IC14A-EN)") (class "Default")
      (node (ref "IC14") (pin "1") (pinfunction "EN_1") (pintype "bidirectional"))
      (node (ref "R38") (pin "2") (pinfunction "2_2") (pintype "passive"))
      (node (ref "~EN_R") (pin "1") (pinfunction "P_1") (pintype "passive"))
    )
    (net (code "63") (name "Net-(IC14A-Y)") (class "Default")
      (node (ref "IC14") (pin "4") (pinfunction "Y_4") (pintype "bidirectional"))
      (node (ref "PWM_RIGHT") (pin "1") (pinfunction "P_1") (pintype "passive"))
    )
    (net (code "64") (name "Net-(IC15A-EN)") (class "Default")
      (node (ref "IC15") (pin "1") (pinfunction "EN_1") (pintype "bidirectional"))
      (node (ref "R37") (pin "2") (pinfunction "2_2") (pintype "passive"))
      (node (ref "~EN_L") (pin "1") (pinfunction "P_1") (pintype "passive"))
    )
    (net (code "65") (name "Net-(IC15A-Y)") (class "Default")
      (node (ref "IC15") (pin "4") (pinfunction "Y_4") (pintype "bidirectional"))
      (node (ref "PWM_LEFT") (pin "1") (pinfunction "P_1") (pintype "passive"))
    )
    (net (code "66") (name "Net-(IC16A-A)") (class "Default")
      (node (ref "IC16") (pin "2") (pinfunction "A_2") (pintype "bidirectional"))
      (node (ref "IC17") (pin "2") (pinfunction "A_2") (pintype "bidirectional"))
      (node (ref "PWM_FB") (pin "1") (pinfunction "P_1") (pintype "passive"))
    )
    (net (code "67") (name "Net-(IC16A-EN)") (class "Default")
      (node (ref "IC16") (pin "1") (pinfunction "EN_1") (pintype "bidirectional"))
      (node (ref "R39") (pin "2") (pinfunction "2_2") (pintype "passive"))
      (node (ref "~EN_FWD") (pin "1") (pinfunction "P_1") (pintype "passive"))
    )
    (net (code "68") (name "Net-(IC16A-Y)") (class "Default")
      (node (ref "IC16") (pin "4") (pinfunction "Y_4") (pintype "bidirectional"))
      (node (ref "PWM_FWD") (pin "1") (pinfunction "P_1") (pintype "passive"))
    )
    (net (code "69") (name "Net-(IC17A-EN)") (class "Default")
      (node (ref "IC17") (pin "1") (pinfunction "EN_1") (pintype "bidirectional"))
      (node (ref "R40") (pin "2") (pinfunction "2_2") (pintype "passive"))
      (node (ref "~EN_BWD") (pin "1") (pinfunction "P_1") (pintype "passive"))
    )
    (net (code "70") (name "Net-(IC17A-Y)") (class "Default")
      (node (ref "IC17") (pin "4") (pinfunction "Y_4") (pintype "bidirectional"))
      (node (ref "PWM_BWD") (pin "1") (pinfunction "P_1") (pintype "passive"))
    )
    (net (code "71") (name "Net-(IC18A--)") (class "Default")
      (node (ref "IC18") (pin "2") (pinfunction "-_2") (pintype "bidirectional"))
      (node (ref "R47") (pin "2") (pinfunction "2_2") (pintype "passive"))
      (node (ref "R48") (pin "2") (pinfunction "2_2") (pintype "passive"))
    )
    (net (code "72") (name "Net-(IC18A-OUT)") (class "Default")
      (node (ref "IC18") (pin "1") (pinfunction "OUT_1") (pintype "bidirectional"))
      (node (ref "IC18") (pin "5") (pinfunction "+_5") (pintype "bidirectional"))
      (node (ref "R47") (pin "1") (pinfunction "1_1") (pintype "passive"))
    )
    (net (code "73") (name "Net-(LED1-PadA)") (class "Default")
      (node (ref "LED1") (pin "A") (pinfunction "A_A") (pintype "passive"))
      (node (ref "R11") (pin "1") (pinfunction "1_1") (pintype "passive"))
    )
    (net (code "74") (name "Net-(PAD9-P)") (class "Default")
      (node (ref "PAD9") (pin "1") (pinfunction "P_1") (pintype "passive"))
      (node (ref "R1") (pin "2") (pinfunction "2_2") (pintype "passive"))
      (node (ref "R3") (pin "2") (pinfunction "2_2") (pintype "passive"))
    )
    (net (code "75") (name "Net-(PAD10-P)") (class "Default")
      (node (ref "PAD10") (pin "1") (pinfunction "P_1") (pintype "passive"))
      (node (ref "R4") (pin "2") (pinfunction "2_2") (pintype "passive"))
      (node (ref "R5") (pin "2") (pinfunction "2_2") (pintype "passive"))
    )
    (net (code "76") (name "Net-(PAD11-P)") (class "Default")
      (node (ref "PAD11") (pin "1") (pinfunction "P_1") (pintype "passive"))
      (node (ref "R7") (pin "2") (pinfunction "2_2") (pintype "passive"))
      (node (ref "R8") (pin "2") (pinfunction "2_2") (pintype "passive"))
    )
    (net (code "77") (name "Net-(PAD12-P)") (class "Default")
      (node (ref "PAD12") (pin "1") (pinfunction "P_1") (pintype "passive"))
      (node (ref "R10") (pin "2") (pinfunction "2_2") (pintype "passive"))
      (node (ref "R9") (pin "2") (pinfunction "2_2") (pintype "passive"))
    )
    (net (code "78") (name "Net-(PAD13-P)") (class "Default")
      (node (ref "PAD13") (pin "1") (pinfunction "P_1") (pintype "passive"))
      (node (ref "R12") (pin "2") (pinfunction "2_2") (pintype "passive"))
      (node (ref "R13") (pin "2") (pinfunction "2_2") (pintype "passive"))
    )
    (net (code "79") (name "Net-(PAD14-P)") (class "Default")
      (node (ref "PAD14") (pin "1") (pinfunction "P_1") (pintype "passive"))
      (node (ref "R14") (pin "2") (pinfunction "2_2") (pintype "passive"))
      (node (ref "R15") (pin "2") (pinfunction "2_2") (pintype "passive"))
    )
    (net (code "80") (name "Net-(PAD15-P)") (class "Default")
      (node (ref "PAD15") (pin "1") (pinfunction "P_1") (pintype "passive"))
      (node (ref "R16") (pin "2") (pinfunction "2_2") (pintype "passive"))
      (node (ref "R17") (pin "2") (pinfunction "2_2") (pintype "passive"))
    )
    (net (code "81") (name "Net-(PAD16-P)") (class "Default")
      (node (ref "PAD16") (pin "1") (pinfunction "P_1") (pintype "passive"))
      (node (ref "R18") (pin "2") (pinfunction "2_2") (pintype "passive"))
      (node (ref "R19") (pin "2") (pinfunction "2_2") (pintype "passive"))
    )
    (net (code "82") (name "Net-(U1-PB6(XTAL1{slash}TOSC1))") (class "Default")
      (node (ref "Q1") (pin "3") (pinfunction "3_3") (pintype "passive"))
      (node (ref "U1") (pin "7") (pinfunction "PB6(XTAL1/TOSC1)_7") (pintype "bidirectional"))
    )
    (net (code "83") (name "Net-(U1-PB7(XTAL2{slash}TOSC2))") (class "Default")
      (node (ref "Q1") (pin "1") (pinfunction "1_1") (pintype "passive"))
      (node (ref "U1") (pin "8") (pinfunction "PB7(XTAL2/TOSC2)_8") (pintype "bidirectional"))
    )
    (net (code "84") (name "VCC") (class "Default")
      (node (ref "C10") (pin "1") (pinfunction "1_1") (pintype "passive"))
      (node (ref "C13") (pin "A") (pinfunction "+_A") (pintype "passive"))
      (node (ref "C3") (pin "2") (pinfunction "2_2") (pintype "passive"))
      (node (ref "IC1") (pin "5") (pinfunction "VCC_5") (pintype "bidirectional"))
      (node (ref "IC10") (pin "5") (pinfunction "VCC_5") (pintype "bidirectional"))
      (node (ref "IC11") (pin "5") (pinfunction "VCC_5") (pintype "bidirectional"))
      (node (ref "IC12") (pin "5") (pinfunction "VCC_5") (pintype "bidirectional"))
      (node (ref "IC15") (pin "5") (pinfunction "VCC_5") (pintype "bidirectional"))
      (node (ref "IC18") (pin "8") (pinfunction "VCC_8") (pintype "bidirectional"))
      (node (ref "IC2") (pin "5") (pinfunction "VCC_5") (pintype "bidirectional"))
      (node (ref "IC3") (pin "5") (pinfunction "VCC_5") (pintype "bidirectional"))
      (node (ref "IC4") (pin "5") (pinfunction "VCC_5") (pintype "bidirectional"))
      (node (ref "IC5") (pin "5") (pinfunction "VCC_5") (pintype "bidirectional"))
      (node (ref "IC6") (pin "5") (pinfunction "VCC_5") (pintype "bidirectional"))
      (node (ref "IC7") (pin "5") (pinfunction "VCC_5") (pintype "bidirectional"))
      (node (ref "IC8") (pin "5") (pinfunction "VCC_5") (pintype "bidirectional"))
      (node (ref "IC9") (pin "8") (pinfunction "VCC_8") (pintype "bidirectional"))
      (node (ref "JP1") (pin "4") (pinfunction "VCC_4") (pintype "passive"))
      (node (ref "JP6") (pin "4") (pinfunction "4_4") (pintype "passive"))
      (node (ref "R11") (pin "2") (pinfunction "2_2") (pintype "passive"))
      (node (ref "R2") (pin "2") (pinfunction "2_2") (pintype "passive"))
      (node (ref "R20") (pin "2") (pinfunction "2_2") (pintype "passive"))
      (node (ref "R27") (pin "2") (pinfunction "2_2") (pintype "passive"))
      (node (ref "U1") (pin "18") (pinfunction "AVCC_18") (pintype "bidirectional"))
      (node (ref "U1") (pin "4") (pinfunction "VCC_4") (pintype "bidirectional"))
      (node (ref "U1") (pin "6") (pinfunction "VCC_6") (pintype "bidirectional"))
      (node (ref "U2") (pin "5") (pinfunction "OUT_5") (pintype "passive"))
      (node (ref "VCC") (pin "1") (pinfunction "P_1") (pintype "passive"))
      (node (ref "VCC1") (pin "1") (pinfunction "P_1") (pintype "passive"))
    )
    (net (code "85") (name "unconnected-(AUDIO_INL1-P-Pad1)") (class "Default")
      (node (ref "AUDIO_INL1") (pin "1") (pinfunction "P_1") (pintype "passive"))
    )
    (net (code "86") (name "unconnected-(U1-ADC6-Pad19)") (class "Default")
      (node (ref "U1") (pin "19") (pinfunction "ADC6_19") (pintype "bidirectional"))
    )
    (net (code "87") (name "unconnected-(U1-ADC7-Pad22)") (class "Default")
      (node (ref "U1") (pin "22") (pinfunction "ADC7_22") (pintype "bidirectional"))
    )
    (net (code "88") (name "unconnected-(U2-BP-Pad4)") (class "Default")
      (node (ref "U2") (pin "4") (pinfunction "BP_4") (pintype "input"))
    )
  )
)
